# 03_MCU.net
KiCad netlist of a schematic drawn in Altium Designer
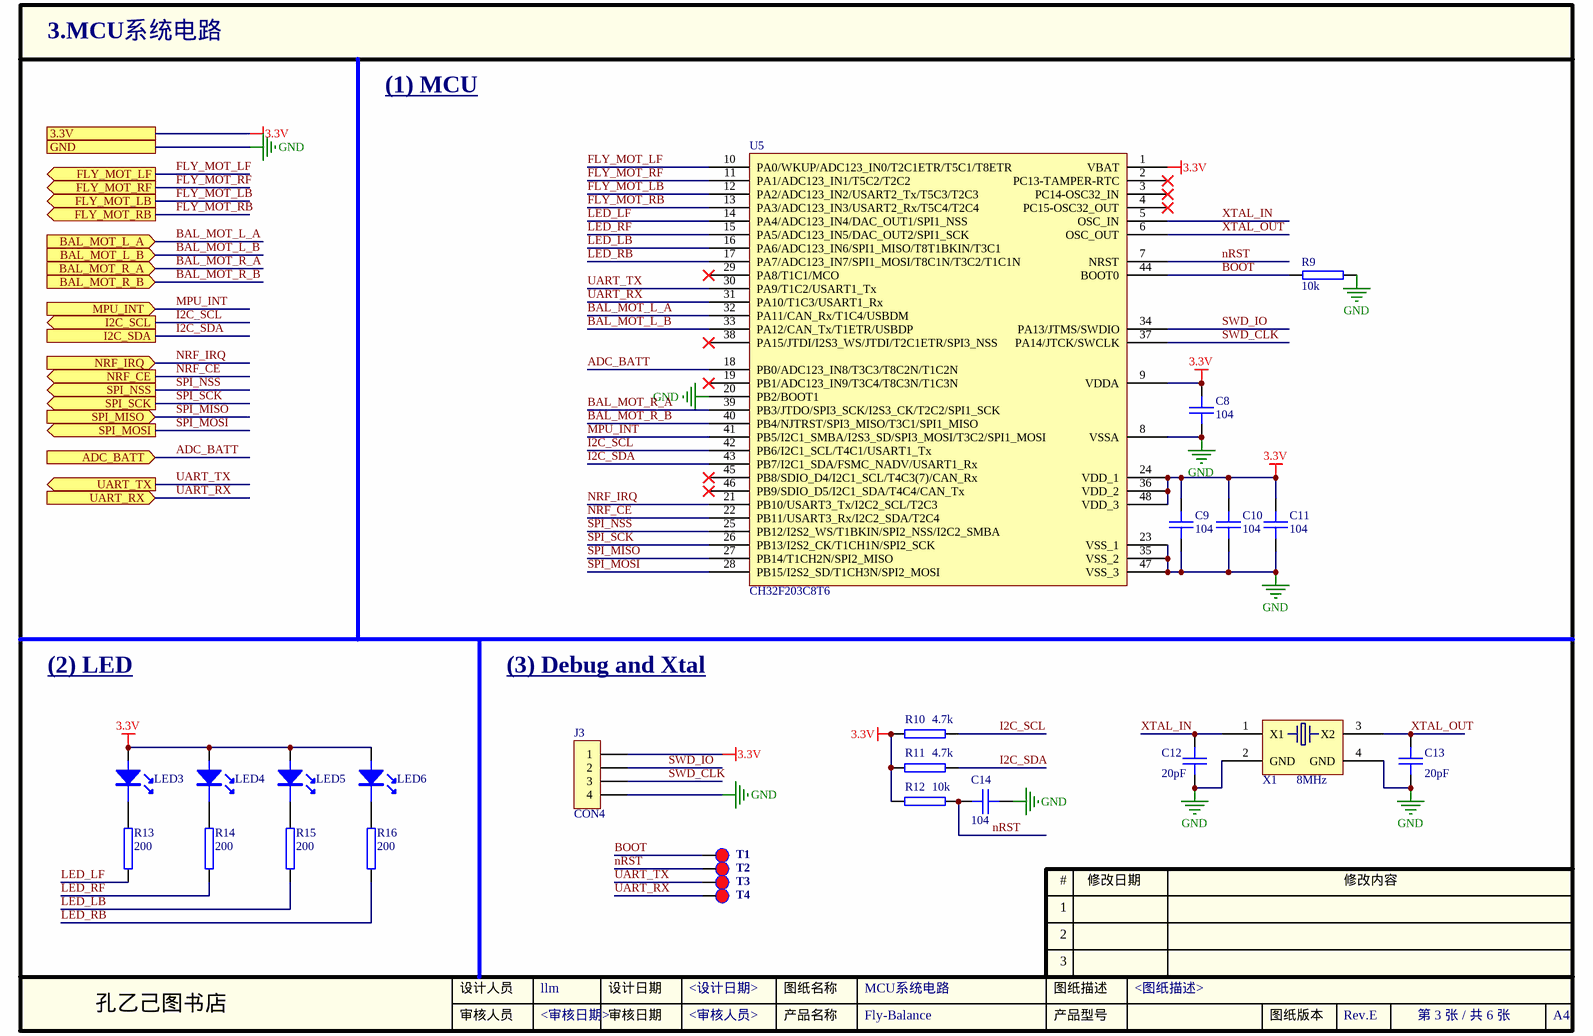
[diagram p0: 03_MCU.SchDoc]

(export (version "E")
  (design (tool "Eeschema 10.0.6"))
  (components
    (comp (ref "C8")
      (value "104")
      (footprint "0402C")
      (description "电容")
      (libsource (lib "MY_Schlib") (part "CAP"))
    )
    (comp (ref "C9")
      (value "104")
      (footprint "0402C")
      (description "电容")
      (libsource (lib "MY_Schlib") (part "CAP"))
    )
    (comp (ref "C10")
      (value "104")
      (footprint "0402C")
      (description "电容")
      (libsource (lib "MY_Schlib") (part "CAP"))
    )
    (comp (ref "C11")
      (value "104")
      (footprint "0402C")
      (description "电容")
      (libsource (lib "MY_Schlib") (part "CAP"))
    )
    (comp (ref "C12")
      (value "20pF")
      (footprint "0402C")
      (description "电容")
      (libsource (lib "MY_Schlib") (part "CAP"))
    )
    (comp (ref "C13")
      (value "20pF")
      (footprint "0402C")
      (description "电容")
      (libsource (lib "MY_Schlib") (part "CAP"))
    )
    (comp (ref "C14")
      (value "104")
      (footprint "0402C")
      (description "电容")
      (libsource (lib "MY_Schlib") (part "CAP"))
    )
    (comp (ref "J3")
      (value "CON4")
      (footprint "SIP-4-2.54")
      (description "Connector")
      (libsource (lib "MY_Schlib") (part "CON4"))
    )
    (comp (ref "LED3")
      (value "Blue")
      (footprint "LED-0603")
      (description "发光二极管")
      (libsource (lib "MY_Schlib") (part "LED"))
    )
    (comp (ref "LED4")
      (value "Blue")
      (footprint "LED-0603")
      (description "发光二极管")
      (libsource (lib "MY_Schlib") (part "LED"))
    )
    (comp (ref "LED5")
      (value "Blue")
      (footprint "LED-0603")
      (description "发光二极管")
      (libsource (lib "MY_Schlib") (part "LED"))
    )
    (comp (ref "LED6")
      (value "Blue")
      (footprint "LED-0603")
      (description "发光二极管")
      (libsource (lib "MY_Schlib") (part "LED"))
    )
    (comp (ref "R9")
      (value "10k")
      (footprint "0402R")
      (description "电阻")
      (libsource (lib "MY_Schlib") (part "RES"))
    )
    (comp (ref "R10")
      (value "4.7k")
      (footprint "0402R")
      (description "电阻")
      (libsource (lib "MY_Schlib") (part "RES"))
    )
    (comp (ref "R11")
      (value "4.7k")
      (footprint "0402R")
      (description "电阻")
      (libsource (lib "MY_Schlib") (part "RES"))
    )
    (comp (ref "R12")
      (value "10k")
      (footprint "0402R")
      (description "电阻")
      (libsource (lib "MY_Schlib") (part "RES"))
    )
    (comp (ref "R13")
      (value "200")
      (footprint "0402R")
      (description "电阻")
      (libsource (lib "MY_Schlib") (part "RES"))
    )
    (comp (ref "R14")
      (value "200")
      (footprint "0402R")
      (description "电阻")
      (libsource (lib "MY_Schlib") (part "RES"))
    )
    (comp (ref "R15")
      (value "200")
      (footprint "0402R")
      (description "电阻")
      (libsource (lib "MY_Schlib") (part "RES"))
    )
    (comp (ref "R16")
      (value "200")
      (footprint "0402R")
      (description "电阻")
      (libsource (lib "MY_Schlib") (part "RES"))
    )
    (comp (ref "T1")
      (value "BOOT")
      (footprint "PAD-40")
      (description "测试点")
      (libsource (lib "MY_Schlib") (part "TEST-DOT"))
    )
    (comp (ref "T2")
      (value "RST")
      (footprint "PAD-40")
      (description "测试点")
      (libsource (lib "MY_Schlib") (part "TEST-DOT"))
    )
    (comp (ref "T3")
      (value "Tx")
      (footprint "PAD-40")
      (description "测试点")
      (libsource (lib "MY_Schlib") (part "TEST-DOT"))
    )
    (comp (ref "T4")
      (value "Rx")
      (footprint "PAD-40")
      (description "测试点")
      (libsource (lib "MY_Schlib") (part "TEST-DOT"))
    )
    (comp (ref "U5")
      (value "CH32F203C8T6")
      (footprint "LQFP-48_7x7")
      (description "STM32单片机48引脚")
      (libsource (lib "MY_Schlib") (part "STM32F103C"))
    )
    (comp (ref "X1")
      (value "8MHz")
      (footprint "OSCCC250X320X80-4N")
      (description "4pin贴片无源晶振")
      (libsource (lib "MY_Schlib") (part "XTAL4"))
    )
  )
  (nets
    (net (code "1") (name "/ADC_BATT") (class "Default")
      (node (ref "U5") (pin "18") (pinfunction "PB0/ADC123_IN8/T3C3/T8C2N/T1C2N_18") (pintype "passive"))
    )
    (net (code "2") (name "/BAL_MOT_L_A") (class "Default")
      (node (ref "U5") (pin "32") (pinfunction "PA11/CAN_Rx/T1C4/USBDM_32") (pintype "passive"))
    )
    (net (code "3") (name "/BAL_MOT_L_B") (class "Default")
      (node (ref "U5") (pin "33") (pinfunction "PA12/CAN_Tx/T1ETR/USBDP_33") (pintype "passive"))
    )
    (net (code "4") (name "/BAL_MOT_R_A") (class "Default")
      (node (ref "U5") (pin "39") (pinfunction "PB3/JTDO/SPI3_SCK/I2S3_CK/T2C2/SPI1_SCK_39") (pintype "passive"))
    )
    (net (code "5") (name "/BAL_MOT_R_B") (class "Default")
      (node (ref "U5") (pin "40") (pinfunction "PB4/NJTRST/SPI3_MISO/T3C1/SPI1_MISO_40") (pintype "passive"))
    )
    (net (code "6") (name "/BOOT") (class "Default")
      (node (ref "R9") (pin "1") (pinfunction "1_1") (pintype "passive"))
      (node (ref "T1") (pin "1") (pinfunction "1_1") (pintype "passive"))
      (node (ref "U5") (pin "44") (pinfunction "BOOT0_44") (pintype "passive"))
    )
    (net (code "7") (name "/FLY_MOT_LB") (class "Default")
      (node (ref "U5") (pin "12") (pinfunction "PA2/ADC123_IN2/USART2_Tx/T5C3/T2C3_12") (pintype "passive"))
    )
    (net (code "8") (name "/FLY_MOT_LF") (class "Default")
      (node (ref "U5") (pin "10") (pinfunction "PA0/WKUP/ADC123_IN0/T2C1ETR/T5C1/T8ETR_10") (pintype "passive"))
    )
    (net (code "9") (name "/FLY_MOT_RB") (class "Default")
      (node (ref "U5") (pin "13") (pinfunction "PA3/ADC123_IN3/USART2_Rx/T5C4/T2C4_13") (pintype "passive"))
    )
    (net (code "10") (name "/FLY_MOT_RF") (class "Default")
      (node (ref "U5") (pin "11") (pinfunction "PA1/ADC123_IN1/T5C2/T2C2_11") (pintype "passive"))
    )
    (net (code "11") (name "/I2C_SCL") (class "Default")
      (node (ref "R10") (pin "1") (pinfunction "1_1") (pintype "passive"))
      (node (ref "U5") (pin "42") (pinfunction "PB6/I2C1_SCL/T4C1/USART1_Tx_42") (pintype "passive"))
    )
    (net (code "12") (name "/I2C_SDA") (class "Default")
      (node (ref "R11") (pin "1") (pinfunction "1_1") (pintype "passive"))
      (node (ref "U5") (pin "43") (pinfunction "PB7/I2C1_SDA/FSMC_NADV/USART1_Rx_43") (pintype "passive"))
    )
    (net (code "13") (name "/LED_LB") (class "Default")
      (node (ref "R15") (pin "1") (pinfunction "1_1") (pintype "passive"))
      (node (ref "U5") (pin "16") (pinfunction "PA6/ADC123_IN6/SPI1_MISO/T8T1BKIN/T3C1_16") (pintype "passive"))
    )
    (net (code "14") (name "/LED_LF") (class "Default")
      (node (ref "R13") (pin "1") (pinfunction "1_1") (pintype "passive"))
      (node (ref "U5") (pin "14") (pinfunction "PA4/ADC123_IN4/DAC_OUT1/SPI1_NSS_14") (pintype "passive"))
    )
    (net (code "15") (name "/LED_RB") (class "Default")
      (node (ref "R16") (pin "1") (pinfunction "1_1") (pintype "passive"))
      (node (ref "U5") (pin "17") (pinfunction "PA7/ADC123_IN7/SPI1_MOSI/T8C1N/T3C2/T1C1N_17") (pintype "passive"))
    )
    (net (code "16") (name "/LED_RF") (class "Default")
      (node (ref "R14") (pin "1") (pinfunction "1_1") (pintype "passive"))
      (node (ref "U5") (pin "15") (pinfunction "PA5/ADC123_IN5/DAC_OUT2/SPI1_SCK_15") (pintype "passive"))
    )
    (net (code "17") (name "/MPU_INT") (class "Default")
      (node (ref "U5") (pin "41") (pinfunction "PB5/I2C1_SMBA/I2S3_SD/SPI3_MOSI/T3C2/SPI1_MOSI_41") (pintype "passive"))
    )
    (net (code "18") (name "/NRF_CE") (class "Default")
      (node (ref "U5") (pin "22") (pinfunction "PB11/USART3_Rx/I2C2_SDA/T2C4_22") (pintype "passive"))
    )
    (net (code "19") (name "/NRF_IRQ") (class "Default")
      (node (ref "U5") (pin "21") (pinfunction "PB10/USART3_Tx/I2C2_SCL/T2C3_21") (pintype "passive"))
    )
    (net (code "20") (name "/SPI_MISO") (class "Default")
      (node (ref "U5") (pin "27") (pinfunction "PB14/T1CH2N/SPI2_MISO_27") (pintype "passive"))
    )
    (net (code "21") (name "/SPI_MOSI") (class "Default")
      (node (ref "U5") (pin "28") (pinfunction "PB15/I2S2_SD/T1CH3N/SPI2_MOSI_28") (pintype "passive"))
    )
    (net (code "22") (name "/SPI_NSS") (class "Default")
      (node (ref "U5") (pin "25") (pinfunction "PB12/I2S2_WS/T1BKIN/SPI2_NSS/I2C2_SMBA_25") (pintype "passive"))
    )
    (net (code "23") (name "/SPI_SCK") (class "Default")
      (node (ref "U5") (pin "26") (pinfunction "PB13/I2S2_CK/T1CH1N/SPI2_SCK_26") (pintype "passive"))
    )
    (net (code "24") (name "/SWD_CLK") (class "Default")
      (node (ref "J3") (pin "3") (pinfunction "3_3") (pintype "passive"))
      (node (ref "U5") (pin "37") (pinfunction "PA14/JTCK/SWCLK_37") (pintype "passive"))
    )
    (net (code "25") (name "/SWD_IO") (class "Default")
      (node (ref "J3") (pin "2") (pinfunction "2_2") (pintype "passive"))
      (node (ref "U5") (pin "34") (pinfunction "PA13/JTMS/SWDIO_34") (pintype "passive"))
    )
    (net (code "26") (name "/UART_RX") (class "Default")
      (node (ref "T4") (pin "1") (pinfunction "1_1") (pintype "passive"))
      (node (ref "U5") (pin "31") (pinfunction "PA10/T1C3/USART1_Rx_31") (pintype "passive"))
    )
    (net (code "27") (name "/UART_TX") (class "Default")
      (node (ref "T3") (pin "1") (pinfunction "1_1") (pintype "passive"))
      (node (ref "U5") (pin "30") (pinfunction "PA9/T1C2/USART1_Tx_30") (pintype "passive"))
    )
    (net (code "28") (name "/XTAL_IN") (class "Default")
      (node (ref "C12") (pin "2") (pinfunction "2_2") (pintype "passive"))
      (node (ref "U5") (pin "5") (pinfunction "OSC_IN_5") (pintype "passive"))
      (node (ref "X1") (pin "1") (pinfunction "X1_1") (pintype "passive"))
    )
    (net (code "29") (name "/XTAL_OUT") (class "Default")
      (node (ref "C13") (pin "2") (pinfunction "2_2") (pintype "passive"))
      (node (ref "U5") (pin "6") (pinfunction "OSC_OUT_6") (pintype "passive"))
      (node (ref "X1") (pin "3") (pinfunction "X2_3") (pintype "passive"))
    )
    (net (code "30") (name "/nRST") (class "Default")
      (node (ref "C14") (pin "2") (pinfunction "2_2") (pintype "passive"))
      (node (ref "R12") (pin "1") (pinfunction "1_1") (pintype "passive"))
      (node (ref "T2") (pin "1") (pinfunction "1_1") (pintype "passive"))
      (node (ref "U5") (pin "7") (pinfunction "NRST_7") (pintype "passive"))
    )
    (net (code "31") (name "3.3V") (class "Default")
      (node (ref "C10") (pin "2") (pinfunction "2_2") (pintype "passive"))
      (node (ref "C11") (pin "2") (pinfunction "2_2") (pintype "passive"))
      (node (ref "C8") (pin "2") (pinfunction "2_2") (pintype "passive"))
      (node (ref "C9") (pin "2") (pinfunction "2_2") (pintype "passive"))
      (node (ref "J3") (pin "1") (pinfunction "1_1") (pintype "passive"))
      (node (ref "LED3") (pin "1") (pinfunction "1_1") (pintype "passive"))
      (node (ref "LED4") (pin "1") (pinfunction "1_1") (pintype "passive"))
      (node (ref "LED5") (pin "1") (pinfunction "1_1") (pintype "passive"))
      (node (ref "LED6") (pin "1") (pinfunction "1_1") (pintype "passive"))
      (node (ref "R10") (pin "2") (pinfunction "2_2") (pintype "passive"))
      (node (ref "R11") (pin "2") (pinfunction "2_2") (pintype "passive"))
      (node (ref "R12") (pin "2") (pinfunction "2_2") (pintype "passive"))
      (node (ref "U5") (pin "1") (pinfunction "VBAT_1") (pintype "passive"))
      (node (ref "U5") (pin "24") (pinfunction "VDD_1_24") (pintype "passive"))
      (node (ref "U5") (pin "36") (pinfunction "VDD_2_36") (pintype "passive"))
      (node (ref "U5") (pin "48") (pinfunction "VDD_3_48") (pintype "passive"))
      (node (ref "U5") (pin "9") (pinfunction "VDDA_9") (pintype "passive"))
    )
    (net (code "32") (name "GND") (class "Default")
      (node (ref "C10") (pin "1") (pinfunction "1_1") (pintype "passive"))
      (node (ref "C11") (pin "1") (pinfunction "1_1") (pintype "passive"))
      (node (ref "C12") (pin "1") (pinfunction "1_1") (pintype "passive"))
      (node (ref "C13") (pin "1") (pinfunction "1_1") (pintype "passive"))
      (node (ref "C14") (pin "1") (pinfunction "1_1") (pintype "passive"))
      (node (ref "C8") (pin "1") (pinfunction "1_1") (pintype "passive"))
      (node (ref "C9") (pin "1") (pinfunction "1_1") (pintype "passive"))
      (node (ref "J3") (pin "4") (pinfunction "4_4") (pintype "passive"))
      (node (ref "R9") (pin "2") (pinfunction "2_2") (pintype "passive"))
      (node (ref "U5") (pin "20") (pinfunction "PB2/BOOT1_20") (pintype "passive"))
      (node (ref "U5") (pin "23") (pinfunction "VSS_1_23") (pintype "passive"))
      (node (ref "U5") (pin "35") (pinfunction "VSS_2_35") (pintype "passive"))
      (node (ref "U5") (pin "47") (pinfunction "VSS_3_47") (pintype "passive"))
      (node (ref "U5") (pin "8") (pinfunction "VSSA_8") (pintype "passive"))
      (node (ref "X1") (pin "2") (pinfunction "GND_2") (pintype "passive"))
      (node (ref "X1") (pin "4") (pinfunction "GND_4") (pintype "passive"))
    )
    (net (code "33") (name "Net-(LED3-Pad2)") (class "Default")
      (node (ref "LED3") (pin "2") (pinfunction "2_2") (pintype "passive"))
      (node (ref "R13") (pin "2") (pinfunction "2_2") (pintype "passive"))
    )
    (net (code "34") (name "Net-(LED4-Pad2)") (class "Default")
      (node (ref "LED4") (pin "2") (pinfunction "2_2") (pintype "passive"))
      (node (ref "R14") (pin "2") (pinfunction "2_2") (pintype "passive"))
    )
    (net (code "35") (name "Net-(LED5-Pad2)") (class "Default")
      (node (ref "LED5") (pin "2") (pinfunction "2_2") (pintype "passive"))
      (node (ref "R15") (pin "2") (pinfunction "2_2") (pintype "passive"))
    )
    (net (code "36") (name "Net-(LED6-Pad2)") (class "Default")
      (node (ref "LED6") (pin "2") (pinfunction "2_2") (pintype "passive"))
      (node (ref "R16") (pin "2") (pinfunction "2_2") (pintype "passive"))
    )
    (net (code "37") (name "unconnected-(U5-PA8{slash}T1C1{slash}MCO-Pad29)") (class "Default")
      (node (ref "U5") (pin "29") (pinfunction "PA8/T1C1/MCO_29") (pintype "passive+no_connect"))
    )
    (net (code "38") (name "unconnected-(U5-PA15{slash}JTDI{slash}I2S3_WS{slash}JTDI{slash}T2C1ETR{slash}SPI3_NSS-Pad38)") (class "Default")
      (node (ref "U5") (pin "38") (pinfunction "PA15/JTDI/I2S3_WS/JTDI/T2C1ETR/SPI3_NSS_38") (pintype "passive+no_connect"))
    )
    (net (code "39") (name "unconnected-(U5-PB1{slash}ADC123_IN9{slash}T3C4{slash}T8C3N{slash}T1C3N-Pad19)") (class "Default")
      (node (ref "U5") (pin "19") (pinfunction "PB1/ADC123_IN9/T3C4/T8C3N/T1C3N_19") (pintype "passive+no_connect"))
    )
    (net (code "40") (name "unconnected-(U5-PB8{slash}SDIO_D4{slash}I2C1_SCL{slash}T4C3(7){slash}CAN_Rx-Pad45)") (class "Default")
      (node (ref "U5") (pin "45") (pinfunction "PB8/SDIO_D4/I2C1_SCL/T4C3(7)/CAN_Rx_45") (pintype "passive+no_connect"))
    )
    (net (code "41") (name "unconnected-(U5-PB9{slash}SDIO_D5{slash}I2C1_SDA{slash}T4C4{slash}CAN_Tx-Pad46)") (class "Default")
      (node (ref "U5") (pin "46") (pinfunction "PB9/SDIO_D5/I2C1_SDA/T4C4/CAN_Tx_46") (pintype "passive+no_connect"))
    )
    (net (code "42") (name "unconnected-(U5-PC13-TAMPER-RTC-Pad2)") (class "Default")
      (node (ref "U5") (pin "2") (pinfunction "PC13-TAMPER-RTC_2") (pintype "passive+no_connect"))
    )
    (net (code "43") (name "unconnected-(U5-PC14-OSC32_IN-Pad3)") (class "Default")
      (node (ref "U5") (pin "3") (pinfunction "PC14-OSC32_IN_3") (pintype "passive+no_connect"))
    )
    (net (code "44") (name "unconnected-(U5-PC15-OSC32_OUT-Pad4)") (class "Default")
      (node (ref "U5") (pin "4") (pinfunction "PC15-OSC32_OUT_4") (pintype "passive+no_connect"))
    )
  )
)
